# Diagrama_secuda_rio.net
KiCad netlist of a schematic drawn in EAGLE
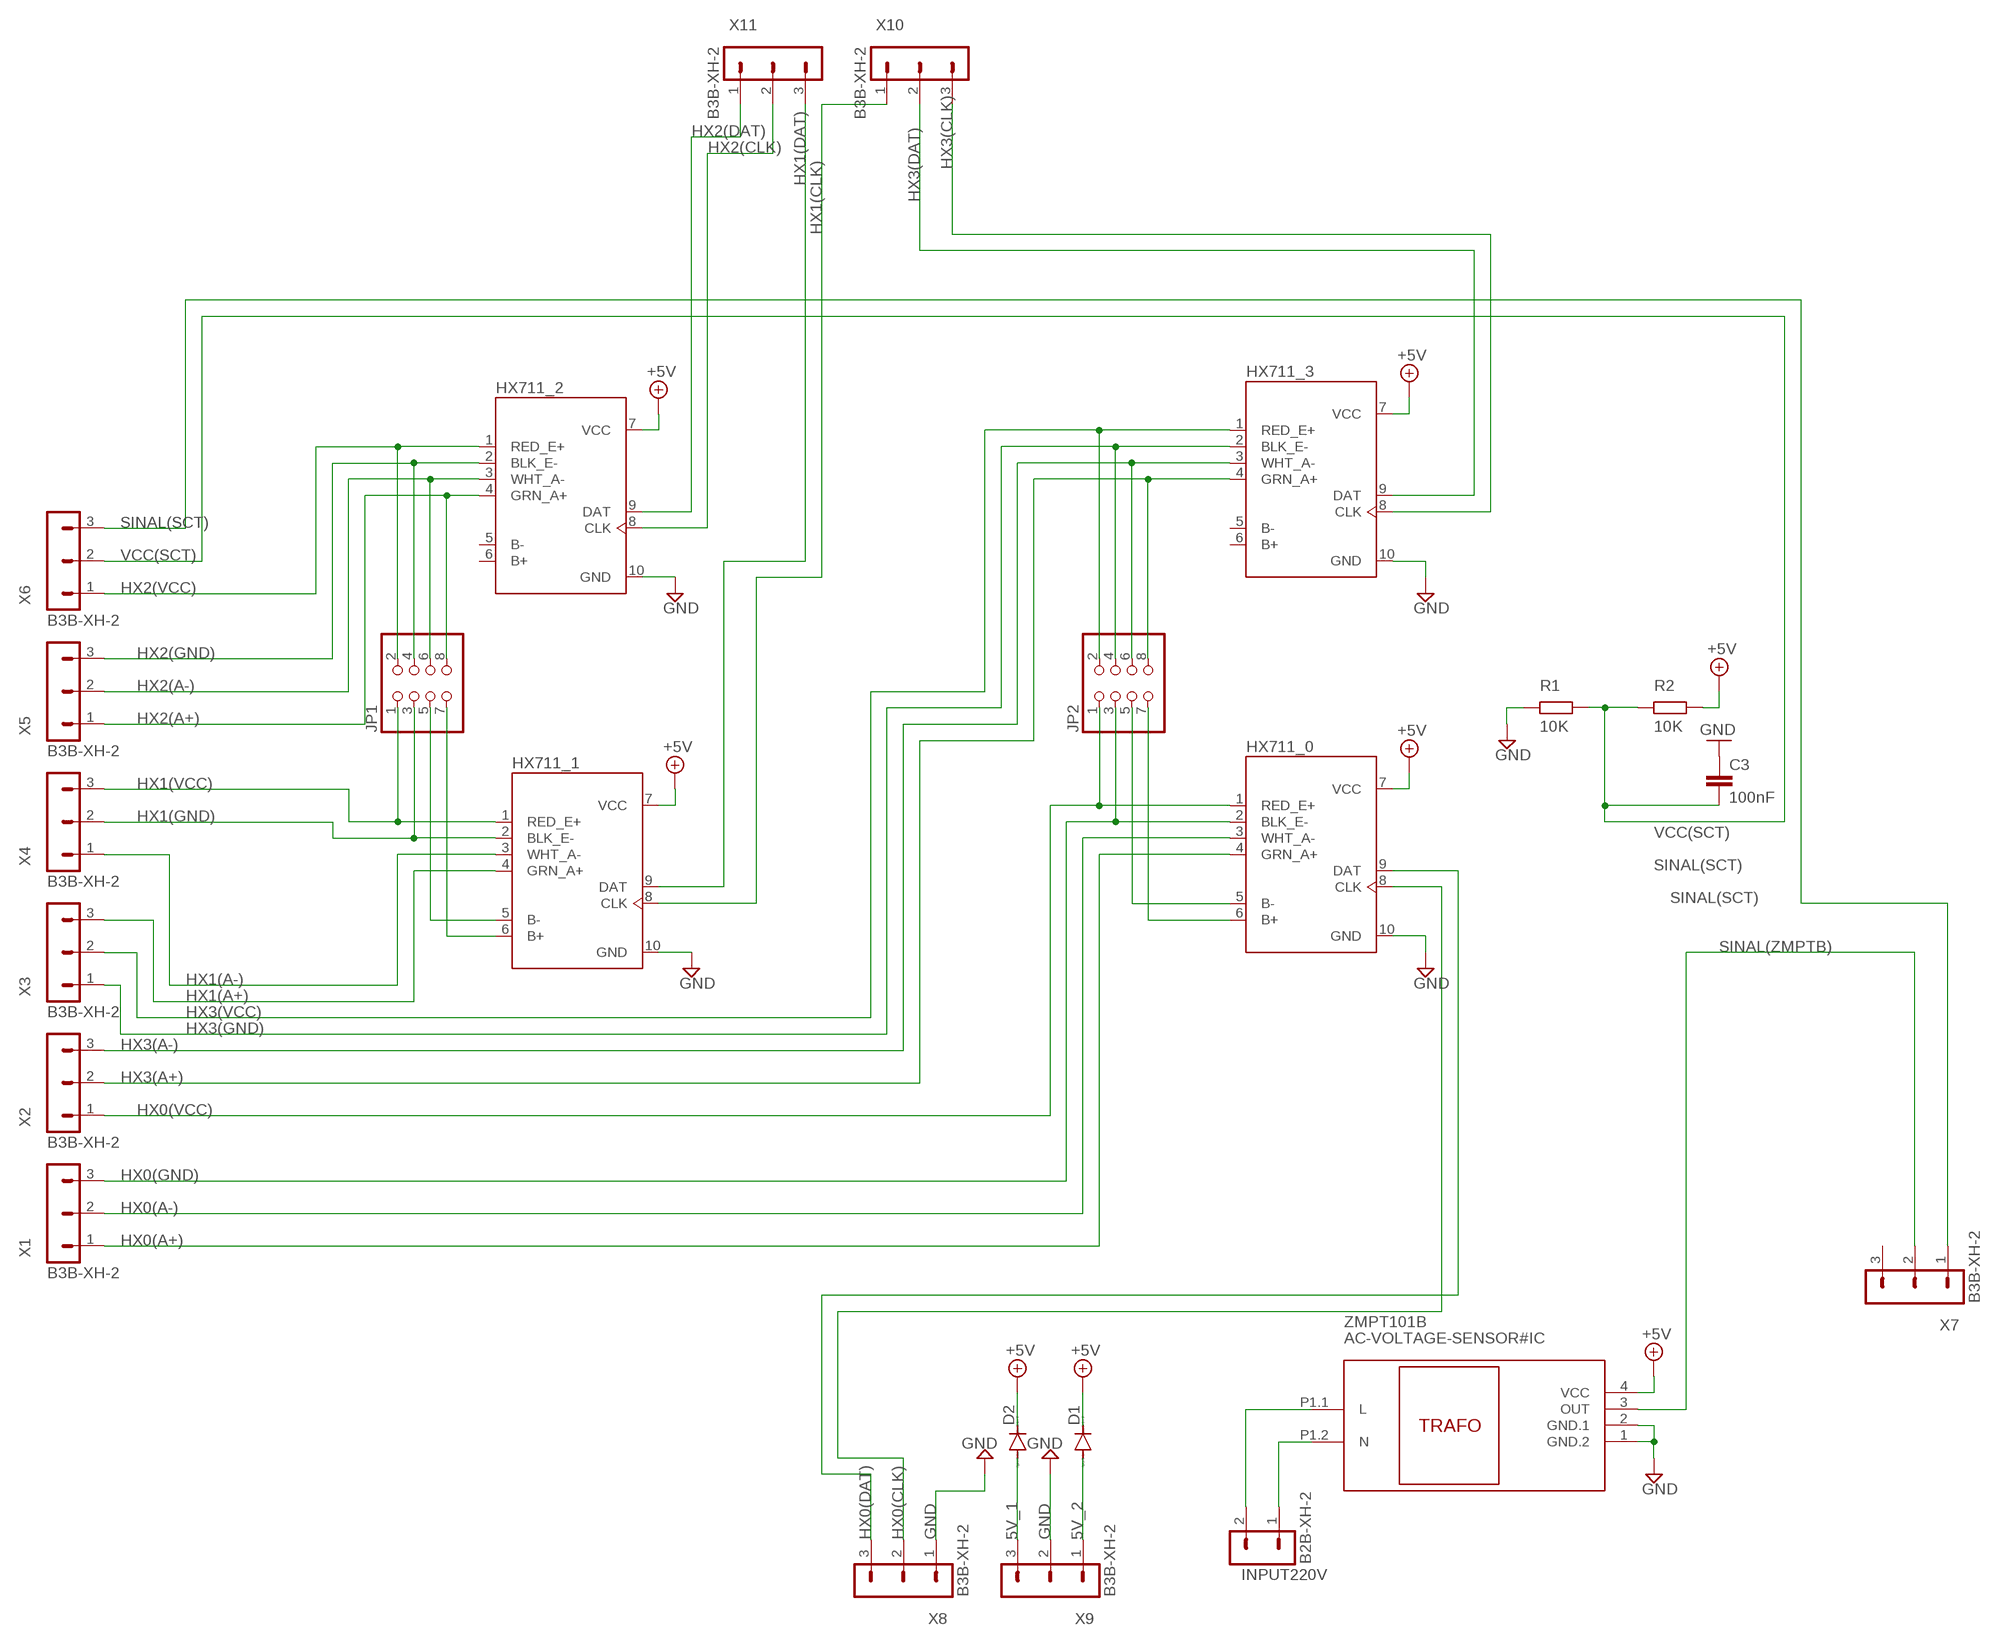
[diagram p0: schematic, sheet 1]

(export (version "E")
  (design (tool "Eeschema 10.0.6"))
  (components
    (comp (ref "C3")
      (value "100nF")
      (footprint "eagle-import:C050-025X075")
      (libsource (lib "eagle-import") (part "C-EU050-025X075"))
    )
    (comp (ref "D1")
      (value "1N4148DO35-7")
      (footprint "eagle-import:DO35-7")
      (fields (field (name "SPICEPREFIX") "D"))
      (libsource (lib "eagle-import") (part "1N4148DO35-7"))
    )
    (comp (ref "D2")
      (value "1")
      (footprint "eagle-import:DO35-7")
      (libsource (lib "eagle-import") (part "1N4148DO35-7"))
    )
    (comp (ref "HX711_0")
      (value "HX711MODULO")
      (footprint "eagle-import:HX711MODULO")
      (fields (field (name "MF") "SparkFun") (field (name "MP") "SEN-13879"))
      (libsource (lib "eagle-import") (part "HX711MODULO"))
    )
    (comp (ref "HX711_1")
      (value "HX711MODULO")
      (footprint "eagle-import:HX711MODULO")
      (fields (field (name "MF") "SparkFun") (field (name "MP") "SEN-13879"))
      (libsource (lib "eagle-import") (part "HX711MODULO"))
    )
    (comp (ref "HX711_2")
      (value "HX711MODULO")
      (footprint "eagle-import:HX711MODULO")
      (fields (field (name "MF") "SparkFun") (field (name "MP") "SEN-13879"))
      (libsource (lib "eagle-import") (part "HX711MODULO"))
    )
    (comp (ref "HX711_3")
      (value "HX711MODULO")
      (footprint "eagle-import:HX711MODULO")
      (fields (field (name "MF") "SparkFun") (field (name "MP") "SEN-13879"))
      (libsource (lib "eagle-import") (part "HX711MODULO"))
    )
    (comp (ref "INPUT220V")
      (value "B2B-XH-2")
      (footprint "eagle-import:B2B-XH-A")
      (libsource (lib "eagle-import") (part "B2B-XH-2"))
    )
    (comp (ref "JP1")
      (value "PINHD-2X4")
      (footprint "eagle-import:2X04")
      (libsource (lib "eagle-import") (part "PINHD-2X4"))
    )
    (comp (ref "JP2")
      (value "PINHD-2X4")
      (footprint "eagle-import:2X04")
      (libsource (lib "eagle-import") (part "PINHD-2X4"))
    )
    (comp (ref "R1")
      (value "10K")
      (footprint "eagle-import:1_4W-0.41K")
      (libsource (lib "eagle-import") (part "1K1/4RESISTOR"))
    )
    (comp (ref "R2")
      (value "10K")
      (footprint "eagle-import:1_4W-0.41K")
      (libsource (lib "eagle-import") (part "1K1/4RESISTOR"))
    )
    (comp (ref "X1")
      (value "B3B-XH-2")
      (footprint "eagle-import:B3B-XH-A")
      (libsource (lib "eagle-import") (part "B3B-XH-2"))
    )
    (comp (ref "X2")
      (value "B3B-XH-2")
      (footprint "eagle-import:B3B-XH-A")
      (libsource (lib "eagle-import") (part "B3B-XH-2"))
    )
    (comp (ref "X3")
      (value "B3B-XH-2")
      (footprint "eagle-import:B3B-XH-A")
      (libsource (lib "eagle-import") (part "B3B-XH-2"))
    )
    (comp (ref "X4")
      (value "B3B-XH-2")
      (footprint "eagle-import:B3B-XH-A")
      (libsource (lib "eagle-import") (part "B3B-XH-2"))
    )
    (comp (ref "X5")
      (value "B3B-XH-2")
      (footprint "eagle-import:B3B-XH-A")
      (libsource (lib "eagle-import") (part "B3B-XH-2"))
    )
    (comp (ref "X6")
      (value "B3B-XH-2")
      (footprint "eagle-import:B3B-XH-A")
      (libsource (lib "eagle-import") (part "B3B-XH-2"))
    )
    (comp (ref "X7")
      (value "B3B-XH-2")
      (footprint "eagle-import:B3B-XH-A")
      (libsource (lib "eagle-import") (part "B3B-XH-2"))
    )
    (comp (ref "X8")
      (value "B3B-XH-2")
      (footprint "eagle-import:B3B-XH-A")
      (libsource (lib "eagle-import") (part "B3B-XH-2"))
    )
    (comp (ref "X9")
      (value "B3B-XH-2")
      (footprint "eagle-import:B3B-XH-A")
      (libsource (lib "eagle-import") (part "B3B-XH-2"))
    )
    (comp (ref "X10")
      (value "B3B-XH-2")
      (footprint "eagle-import:B3B-XH-A")
      (libsource (lib "eagle-import") (part "B3B-XH-2"))
    )
    (comp (ref "X11")
      (value "B3B-XH-2")
      (footprint "eagle-import:B3B-XH-A")
      (libsource (lib "eagle-import") (part "B3B-XH-2"))
    )
    (comp (ref "ZMPT101B")
      (value "AC-VOLTAGE-SENSOR#IC")
      (footprint "eagle-import:AC-VOLTAGE-SENSOR#IC")
      (libsource (lib "eagle-import") (part "AC-VOLTAGE-SENSOR#IC"))
    )
  )
  (nets
    (net (code "1") (name "+5V") (class "Default")
      (node (ref "D1") (pin "C") (pinfunction "C_C") (pintype "passive"))
      (node (ref "D2") (pin "C") (pinfunction "C_C") (pintype "passive"))
      (node (ref "HX711_0") (pin "7") (pinfunction "VCC_7") (pintype "power_in"))
      (node (ref "HX711_1") (pin "7") (pinfunction "VCC_7") (pintype "power_in"))
      (node (ref "HX711_2") (pin "7") (pinfunction "VCC_7") (pintype "power_in"))
      (node (ref "HX711_3") (pin "7") (pinfunction "VCC_7") (pintype "power_in"))
      (node (ref "R2") (pin "2") (pinfunction "2_2") (pintype "passive"))
      (node (ref "ZMPT101B") (pin "4") (pinfunction "VCC_4") (pintype "power_in"))
    )
    (net (code "2") (name "/5V_1") (class "Default")
      (node (ref "D2") (pin "A") (pinfunction "A_A") (pintype "passive"))
      (node (ref "X9") (pin "3") (pinfunction "3_3") (pintype "passive"))
    )
    (net (code "3") (name "/5V_2") (class "Default")
      (node (ref "D1") (pin "A") (pinfunction "A_A") (pintype "passive"))
      (node (ref "X9") (pin "1") (pinfunction "1_1") (pintype "passive"))
    )
    (net (code "4") (name "/HX0(A+)") (class "Default")
      (node (ref "HX711_0") (pin "4") (pinfunction "GRN_A+_4") (pintype "input"))
      (node (ref "X1") (pin "1") (pinfunction "1_1") (pintype "passive"))
    )
    (net (code "5") (name "/HX0(A-)") (class "Default")
      (node (ref "HX711_0") (pin "3") (pinfunction "WHT_A-_3") (pintype "input"))
      (node (ref "X1") (pin "2") (pinfunction "2_2") (pintype "passive"))
    )
    (net (code "6") (name "/HX0(CLK)") (class "Default")
      (node (ref "HX711_0") (pin "8") (pinfunction "CLK_8") (pintype "input"))
      (node (ref "X8") (pin "2") (pinfunction "2_2") (pintype "passive"))
    )
    (net (code "7") (name "/HX0(DAT)") (class "Default")
      (node (ref "HX711_0") (pin "9") (pinfunction "DAT_9") (pintype "output"))
      (node (ref "X8") (pin "3") (pinfunction "3_3") (pintype "passive"))
    )
    (net (code "8") (name "/HX0(GND)") (class "Default")
      (node (ref "HX711_0") (pin "2") (pinfunction "BLK_E-_2") (pintype "bidirectional"))
      (node (ref "JP2") (pin "3") (pinfunction "3_3") (pintype "passive"))
      (node (ref "X1") (pin "3") (pinfunction "3_3") (pintype "passive"))
    )
    (net (code "9") (name "/HX0(VCC)") (class "Default")
      (node (ref "HX711_0") (pin "1") (pinfunction "RED_E+_1") (pintype "bidirectional"))
      (node (ref "JP2") (pin "1") (pinfunction "1_1") (pintype "passive"))
      (node (ref "X2") (pin "1") (pinfunction "1_1") (pintype "passive"))
    )
    (net (code "10") (name "/HX1(A+)") (class "Default")
      (node (ref "HX711_1") (pin "4") (pinfunction "GRN_A+_4") (pintype "input"))
      (node (ref "X3") (pin "3") (pinfunction "3_3") (pintype "passive"))
    )
    (net (code "11") (name "/HX1(A-)") (class "Default")
      (node (ref "HX711_1") (pin "3") (pinfunction "WHT_A-_3") (pintype "input"))
      (node (ref "X4") (pin "1") (pinfunction "1_1") (pintype "passive"))
    )
    (net (code "12") (name "/HX1(CLK)") (class "Default")
      (node (ref "HX711_1") (pin "8") (pinfunction "CLK_8") (pintype "input"))
      (node (ref "X10") (pin "1") (pinfunction "1_1") (pintype "passive"))
    )
    (net (code "13") (name "/HX1(DAT)") (class "Default")
      (node (ref "HX711_1") (pin "9") (pinfunction "DAT_9") (pintype "output"))
      (node (ref "X11") (pin "3") (pinfunction "3_3") (pintype "passive"))
    )
    (net (code "14") (name "/HX1(GND)") (class "Default")
      (node (ref "HX711_1") (pin "2") (pinfunction "BLK_E-_2") (pintype "bidirectional"))
      (node (ref "JP1") (pin "3") (pinfunction "3_3") (pintype "passive"))
      (node (ref "X4") (pin "2") (pinfunction "2_2") (pintype "passive"))
    )
    (net (code "15") (name "/HX1(VCC)") (class "Default")
      (node (ref "HX711_1") (pin "1") (pinfunction "RED_E+_1") (pintype "bidirectional"))
      (node (ref "JP1") (pin "1") (pinfunction "1_1") (pintype "passive"))
      (node (ref "X4") (pin "3") (pinfunction "3_3") (pintype "passive"))
    )
    (net (code "16") (name "/HX2(A+)") (class "Default")
      (node (ref "HX711_2") (pin "4") (pinfunction "GRN_A+_4") (pintype "input"))
      (node (ref "JP1") (pin "8") (pinfunction "8_8") (pintype "passive"))
      (node (ref "X5") (pin "1") (pinfunction "1_1") (pintype "passive"))
    )
    (net (code "17") (name "/HX2(A-)") (class "Default")
      (node (ref "HX711_2") (pin "3") (pinfunction "WHT_A-_3") (pintype "input"))
      (node (ref "JP1") (pin "6") (pinfunction "6_6") (pintype "passive"))
      (node (ref "X5") (pin "2") (pinfunction "2_2") (pintype "passive"))
    )
    (net (code "18") (name "/HX2(CLK)") (class "Default")
      (node (ref "HX711_2") (pin "8") (pinfunction "CLK_8") (pintype "input"))
      (node (ref "X11") (pin "2") (pinfunction "2_2") (pintype "passive"))
    )
    (net (code "19") (name "/HX2(DAT)") (class "Default")
      (node (ref "HX711_2") (pin "9") (pinfunction "DAT_9") (pintype "output"))
      (node (ref "X11") (pin "1") (pinfunction "1_1") (pintype "passive"))
    )
    (net (code "20") (name "/HX2(GND)") (class "Default")
      (node (ref "HX711_2") (pin "2") (pinfunction "BLK_E-_2") (pintype "bidirectional"))
      (node (ref "JP1") (pin "4") (pinfunction "4_4") (pintype "passive"))
      (node (ref "X5") (pin "3") (pinfunction "3_3") (pintype "passive"))
    )
    (net (code "21") (name "/HX2(VCC)") (class "Default")
      (node (ref "HX711_2") (pin "1") (pinfunction "RED_E+_1") (pintype "bidirectional"))
      (node (ref "JP1") (pin "2") (pinfunction "2_2") (pintype "passive"))
      (node (ref "X6") (pin "1") (pinfunction "1_1") (pintype "passive"))
    )
    (net (code "22") (name "/HX3(A+)") (class "Default")
      (node (ref "HX711_3") (pin "4") (pinfunction "GRN_A+_4") (pintype "input"))
      (node (ref "JP2") (pin "8") (pinfunction "8_8") (pintype "passive"))
      (node (ref "X2") (pin "2") (pinfunction "2_2") (pintype "passive"))
    )
    (net (code "23") (name "/HX3(A-)") (class "Default")
      (node (ref "HX711_3") (pin "3") (pinfunction "WHT_A-_3") (pintype "input"))
      (node (ref "JP2") (pin "6") (pinfunction "6_6") (pintype "passive"))
      (node (ref "X2") (pin "3") (pinfunction "3_3") (pintype "passive"))
    )
    (net (code "24") (name "/HX3(CLK)") (class "Default")
      (node (ref "HX711_3") (pin "8") (pinfunction "CLK_8") (pintype "input"))
      (node (ref "X10") (pin "3") (pinfunction "3_3") (pintype "passive"))
    )
    (net (code "25") (name "/HX3(DAT)") (class "Default")
      (node (ref "HX711_3") (pin "9") (pinfunction "DAT_9") (pintype "output"))
      (node (ref "X10") (pin "2") (pinfunction "2_2") (pintype "passive"))
    )
    (net (code "26") (name "/HX3(GND)") (class "Default")
      (node (ref "HX711_3") (pin "2") (pinfunction "BLK_E-_2") (pintype "bidirectional"))
      (node (ref "JP2") (pin "4") (pinfunction "4_4") (pintype "passive"))
      (node (ref "X3") (pin "1") (pinfunction "1_1") (pintype "passive"))
    )
    (net (code "27") (name "/HX3(VCC)") (class "Default")
      (node (ref "HX711_3") (pin "1") (pinfunction "RED_E+_1") (pintype "bidirectional"))
      (node (ref "JP2") (pin "2") (pinfunction "2_2") (pintype "passive"))
      (node (ref "X3") (pin "2") (pinfunction "2_2") (pintype "passive"))
    )
    (net (code "28") (name "/SINAL(SCT)") (class "Default")
      (node (ref "X6") (pin "3") (pinfunction "3_3") (pintype "passive"))
      (node (ref "X7") (pin "1") (pinfunction "1_1") (pintype "passive"))
    )
    (net (code "29") (name "/SINAL(ZMPTB)") (class "Default")
      (node (ref "X7") (pin "2") (pinfunction "2_2") (pintype "passive"))
      (node (ref "ZMPT101B") (pin "3") (pinfunction "OUT_3") (pintype "output"))
    )
    (net (code "30") (name "/VCC(SCT)") (class "Default")
      (node (ref "C3") (pin "2") (pinfunction "2_2") (pintype "passive"))
      (node (ref "R1") (pin "2") (pinfunction "2_2") (pintype "passive"))
      (node (ref "R2") (pin "1") (pinfunction "1_1") (pintype "passive"))
      (node (ref "X6") (pin "2") (pinfunction "2_2") (pintype "passive"))
    )
    (net (code "31") (name "GND") (class "Default")
      (node (ref "C3") (pin "1") (pinfunction "1_1") (pintype "passive"))
      (node (ref "HX711_0") (pin "10") (pinfunction "GND_10") (pintype "power_in"))
      (node (ref "HX711_1") (pin "10") (pinfunction "GND_10") (pintype "power_in"))
      (node (ref "HX711_2") (pin "10") (pinfunction "GND_10") (pintype "power_in"))
      (node (ref "HX711_3") (pin "10") (pinfunction "GND_10") (pintype "power_in"))
      (node (ref "R1") (pin "1") (pinfunction "1_1") (pintype "passive"))
      (node (ref "X8") (pin "1") (pinfunction "1_1") (pintype "passive"))
      (node (ref "X9") (pin "2") (pinfunction "2_2") (pintype "passive"))
      (node (ref "ZMPT101B") (pin "1") (pinfunction "GND.2_1") (pintype "power_in"))
      (node (ref "ZMPT101B") (pin "2") (pinfunction "GND.1_2") (pintype "power_in"))
    )
    (net (code "32") (name "Net-(HX711_0-B+)") (class "Default")
      (node (ref "HX711_0") (pin "6") (pinfunction "B+_6") (pintype "input"))
      (node (ref "JP2") (pin "7") (pinfunction "7_7") (pintype "passive"))
    )
    (net (code "33") (name "Net-(HX711_0-B-)") (class "Default")
      (node (ref "HX711_0") (pin "5") (pinfunction "B-_5") (pintype "input"))
      (node (ref "JP2") (pin "5") (pinfunction "5_5") (pintype "passive"))
    )
    (net (code "34") (name "Net-(HX711_1-B+)") (class "Default")
      (node (ref "HX711_1") (pin "6") (pinfunction "B+_6") (pintype "input"))
      (node (ref "JP1") (pin "7") (pinfunction "7_7") (pintype "passive"))
    )
    (net (code "35") (name "Net-(HX711_1-B-)") (class "Default")
      (node (ref "HX711_1") (pin "5") (pinfunction "B-_5") (pintype "input"))
      (node (ref "JP1") (pin "5") (pinfunction "5_5") (pintype "passive"))
    )
    (net (code "36") (name "Net-(ZMPT101B-L)") (class "Default")
      (node (ref "INPUT220V") (pin "2") (pinfunction "2_2") (pintype "passive"))
      (node (ref "ZMPT101B") (pin "P1.1") (pinfunction "L_P1.1") (pintype "passive"))
    )
    (net (code "37") (name "Net-(ZMPT101B-N)") (class "Default")
      (node (ref "INPUT220V") (pin "1") (pinfunction "1_1") (pintype "passive"))
      (node (ref "ZMPT101B") (pin "P1.2") (pinfunction "N_P1.2") (pintype "passive"))
    )
    (net (code "38") (name "unconnected-(HX711_2-B+-Pad6)") (class "Default")
      (node (ref "HX711_2") (pin "6") (pinfunction "B+_6") (pintype "input"))
    )
    (net (code "39") (name "unconnected-(HX711_2-B--Pad5)") (class "Default")
      (node (ref "HX711_2") (pin "5") (pinfunction "B-_5") (pintype "input"))
    )
    (net (code "40") (name "unconnected-(HX711_3-B+-Pad6)") (class "Default")
      (node (ref "HX711_3") (pin "6") (pinfunction "B+_6") (pintype "input"))
    )
    (net (code "41") (name "unconnected-(HX711_3-B--Pad5)") (class "Default")
      (node (ref "HX711_3") (pin "5") (pinfunction "B-_5") (pintype "input"))
    )
    (net (code "42") (name "unconnected-(X7-Pad3)") (class "Default")
      (node (ref "X7") (pin "3") (pinfunction "3_3") (pintype "passive"))
    )
  )
)
